# tag_key.net
KiCad netlist of a schematic drawn in EAGLE
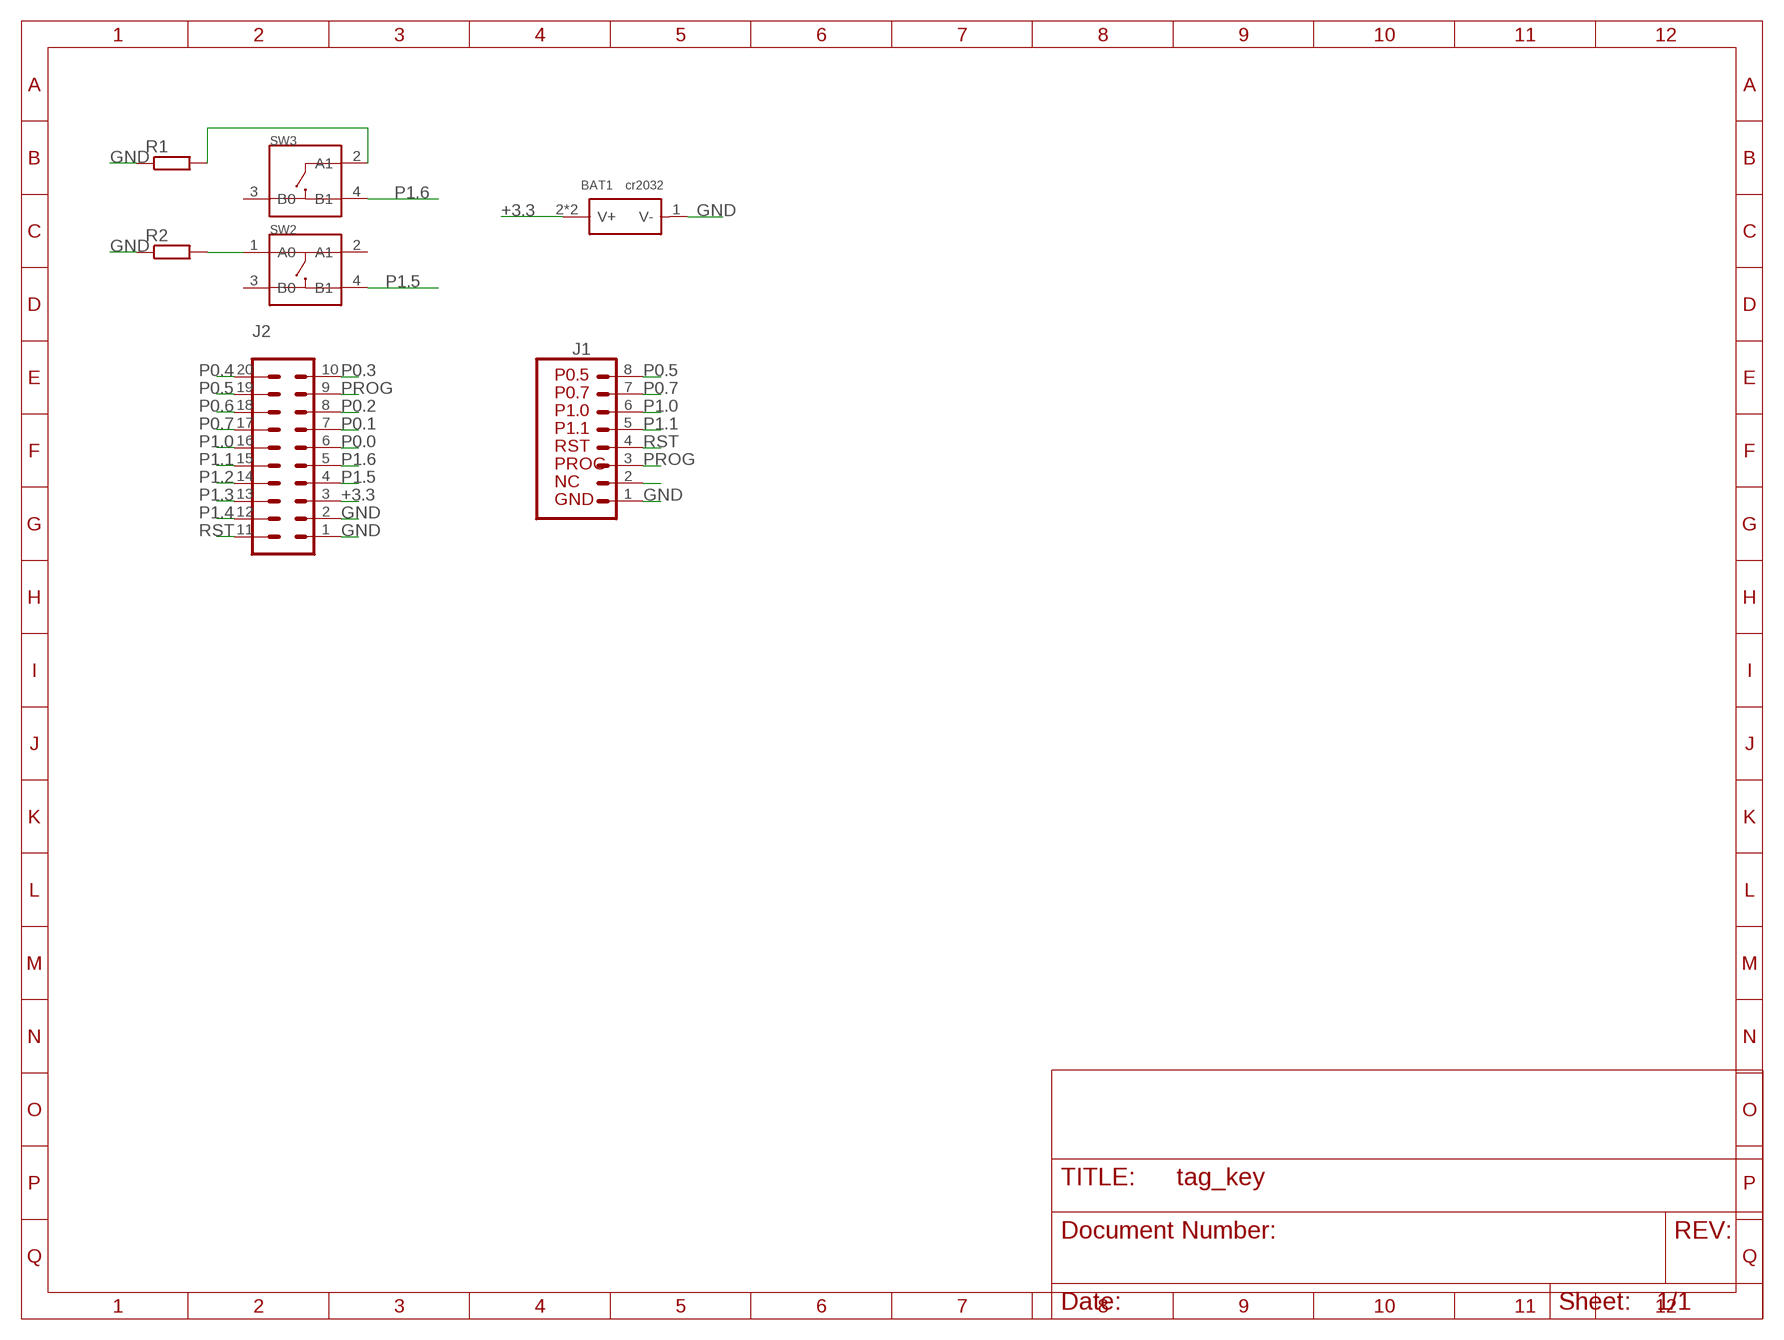
[diagram p0: schematic, sheet 1]

(export (version "E")
  (design (tool "Eeschema 10.0.6"))
  (components
    (comp (ref "BAT1")
      (value "cr2032")
      (footprint "eagle-import:SEEED-OPL-CONNECTOR_BAT2P-20.32-CR2032")
      (libsource (lib "eagle-import") (part "SEEED-OPL-CONNECTOR_DIP-BATTERY-CELL-HOLDER(2032)"))
    )
    (comp (ref "J1")
      (value "SPARKFUN-CONNECTORS_CONN_08\"")
      (footprint "eagle-import:SPARKFUN-CONNECTORS_1X08")
      (libsource (lib "eagle-import") (part "SPARKFUN-CONNECTORS_CONN_08{dblquote}"))
    )
    (comp (ref "J2")
      (value "SPARKFUN-CONNECTORS_CONN_11_1.27MM")
      (footprint "eagle-import:SPARKFUN-CONNECTORS_1X11-1.27MM")
      (libsource (lib "eagle-import") (part "SPARKFUN-CONNECTORS_CONN_11_1.27MM"))
    )
    (comp (ref "R1")
      (value "RESISTOR_R-EU_M0805")
      (footprint "eagle-import:RESISTOR_M0805")
      (libsource (lib "eagle-import") (part "RESISTOR_R-EU_M0805"))
    )
    (comp (ref "R2")
      (value "RESISTOR_R-EU_M0805")
      (footprint "eagle-import:RESISTOR_M0805")
      (libsource (lib "eagle-import") (part "RESISTOR_R-EU_M0805"))
    )
    (comp (ref "SW2")
      (value "SEEED-OPL-SWITCH_SMD-BUTTON(4P-6.0X6.0X7.5MM)")
      (footprint "eagle-import:SEEED-OPL-SWITCH_SW4-SMD-4.5-6.0X6.0X7.5MM")
      (libsource (lib "eagle-import") (part "SEEED-OPL-SWITCH_SMD-BUTTON(4P-6.0X6.0X7.5MM)"))
    )
    (comp (ref "SW3")
      (value "SEEED-OPL-SWITCH_SMD-BUTTON(4P-6.0X6.0X3LEGM)")
      (footprint "eagle-import:SEEED-OPL-SWITCH_SW4-SMD-4.5-6.0X6.0_3LEG")
      (libsource (lib "eagle-import") (part "SEEED-OPL-SWITCH_SMD-BUTTON(4P-6.0X6.0X3LEGM)"))
    )
  )
  (nets
    (net (code "1") (name "/+3.3") (class "Default")
      (node (ref "BAT1") (pin "2") (pinfunction "V+_2") (pintype "bidirectional"))
      (node (ref "BAT1") (pin "3") (pinfunction "V+_3") (pintype "bidirectional"))
      (node (ref "J2") (pin "3") (pinfunction "3_3") (pintype "passive"))
    )
    (net (code "2") (name "/GND") (class "Default")
      (node (ref "BAT1") (pin "1") (pinfunction "V-_1") (pintype "bidirectional"))
      (node (ref "J1") (pin "1") (pinfunction "1_1") (pintype "passive"))
      (node (ref "J2") (pin "1") (pinfunction "1_1") (pintype "passive"))
      (node (ref "J2") (pin "2") (pinfunction "2_2") (pintype "passive"))
      (node (ref "R1") (pin "1") (pinfunction "1_1") (pintype "passive"))
      (node (ref "R2") (pin "1") (pinfunction "1_1") (pintype "passive"))
    )
    (net (code "3") (name "/P0.0") (class "Default")
      (node (ref "J2") (pin "6") (pinfunction "6_6") (pintype "passive"))
    )
    (net (code "4") (name "/P0.1") (class "Default")
      (node (ref "J2") (pin "7") (pinfunction "7_7") (pintype "passive"))
    )
    (net (code "5") (name "/P0.2") (class "Default")
      (node (ref "J2") (pin "8") (pinfunction "8_8") (pintype "passive"))
    )
    (net (code "6") (name "/P0.3") (class "Default")
      (node (ref "J2") (pin "10") (pinfunction "10_10") (pintype "passive"))
    )
    (net (code "7") (name "/P0.4") (class "Default")
      (node (ref "J2") (pin "20") (pinfunction "11_20") (pintype "passive"))
    )
    (net (code "8") (name "/P0.5") (class "Default")
      (node (ref "J1") (pin "8") (pinfunction "8_8") (pintype "passive"))
      (node (ref "J2") (pin "19") (pinfunction "12_19") (pintype "passive"))
    )
    (net (code "9") (name "/P0.6") (class "Default")
      (node (ref "J2") (pin "18") (pinfunction "13_18") (pintype "passive"))
    )
    (net (code "10") (name "/P0.7") (class "Default")
      (node (ref "J1") (pin "7") (pinfunction "7_7") (pintype "passive"))
      (node (ref "J2") (pin "17") (pinfunction "14_17") (pintype "passive"))
    )
    (net (code "11") (name "/P1.0") (class "Default")
      (node (ref "J1") (pin "6") (pinfunction "6_6") (pintype "passive"))
      (node (ref "J2") (pin "16") (pinfunction "15_16") (pintype "passive"))
    )
    (net (code "12") (name "/P1.1") (class "Default")
      (node (ref "J1") (pin "5") (pinfunction "5_5") (pintype "passive"))
      (node (ref "J2") (pin "15") (pinfunction "16_15") (pintype "passive"))
    )
    (net (code "13") (name "/P1.2") (class "Default")
      (node (ref "J2") (pin "14") (pinfunction "17_14") (pintype "passive"))
    )
    (net (code "14") (name "/P1.3") (class "Default")
      (node (ref "J2") (pin "13") (pinfunction "18_13") (pintype "passive"))
    )
    (net (code "15") (name "/P1.4") (class "Default")
      (node (ref "J2") (pin "12") (pinfunction "19_12") (pintype "passive"))
    )
    (net (code "16") (name "/P1.5") (class "Default")
      (node (ref "J2") (pin "4") (pinfunction "4_4") (pintype "passive"))
      (node (ref "SW2") (pin "4") (pinfunction "B1_4") (pintype "bidirectional"))
    )
    (net (code "17") (name "/P1.6") (class "Default")
      (node (ref "J2") (pin "5") (pinfunction "5_5") (pintype "passive"))
      (node (ref "SW3") (pin "4") (pinfunction "B1_4") (pintype "bidirectional"))
    )
    (net (code "18") (name "/PROG") (class "Default")
      (node (ref "J1") (pin "3") (pinfunction "3_3") (pintype "passive"))
      (node (ref "J2") (pin "9") (pinfunction "9_9") (pintype "passive"))
    )
    (net (code "19") (name "/RST") (class "Default")
      (node (ref "J1") (pin "4") (pinfunction "4_4") (pintype "passive"))
      (node (ref "J2") (pin "11") (pinfunction "20_11") (pintype "passive"))
    )
    (net (code "20") (name "Net-(SW2-A0)") (class "Default")
      (node (ref "R2") (pin "2") (pinfunction "2_2") (pintype "passive"))
      (node (ref "SW2") (pin "1") (pinfunction "A0_1") (pintype "bidirectional"))
    )
    (net (code "21") (name "Net-(SW3-A1)") (class "Default")
      (node (ref "R1") (pin "2") (pinfunction "2_2") (pintype "passive"))
      (node (ref "SW3") (pin "2") (pinfunction "A1_2") (pintype "bidirectional"))
    )
    (net (code "22") (name "unconnected-(J1-Pad2)") (class "Default")
      (node (ref "J1") (pin "2") (pinfunction "2_2") (pintype "passive"))
    )
    (net (code "23") (name "unconnected-(SW2-A1-Pad2)") (class "Default")
      (node (ref "SW2") (pin "2") (pinfunction "A1_2") (pintype "bidirectional"))
    )
    (net (code "24") (name "unconnected-(SW2-B0-Pad3)") (class "Default")
      (node (ref "SW2") (pin "3") (pinfunction "B0_3") (pintype "bidirectional"))
    )
    (net (code "25") (name "unconnected-(SW3-B0-Pad3)") (class "Default")
      (node (ref "SW3") (pin "3") (pinfunction "B0_3") (pintype "bidirectional"))
    )
  )
)
